# HF_FrontEndOverview.net
KiCad netlist of a schematic drawn in Altium Designer
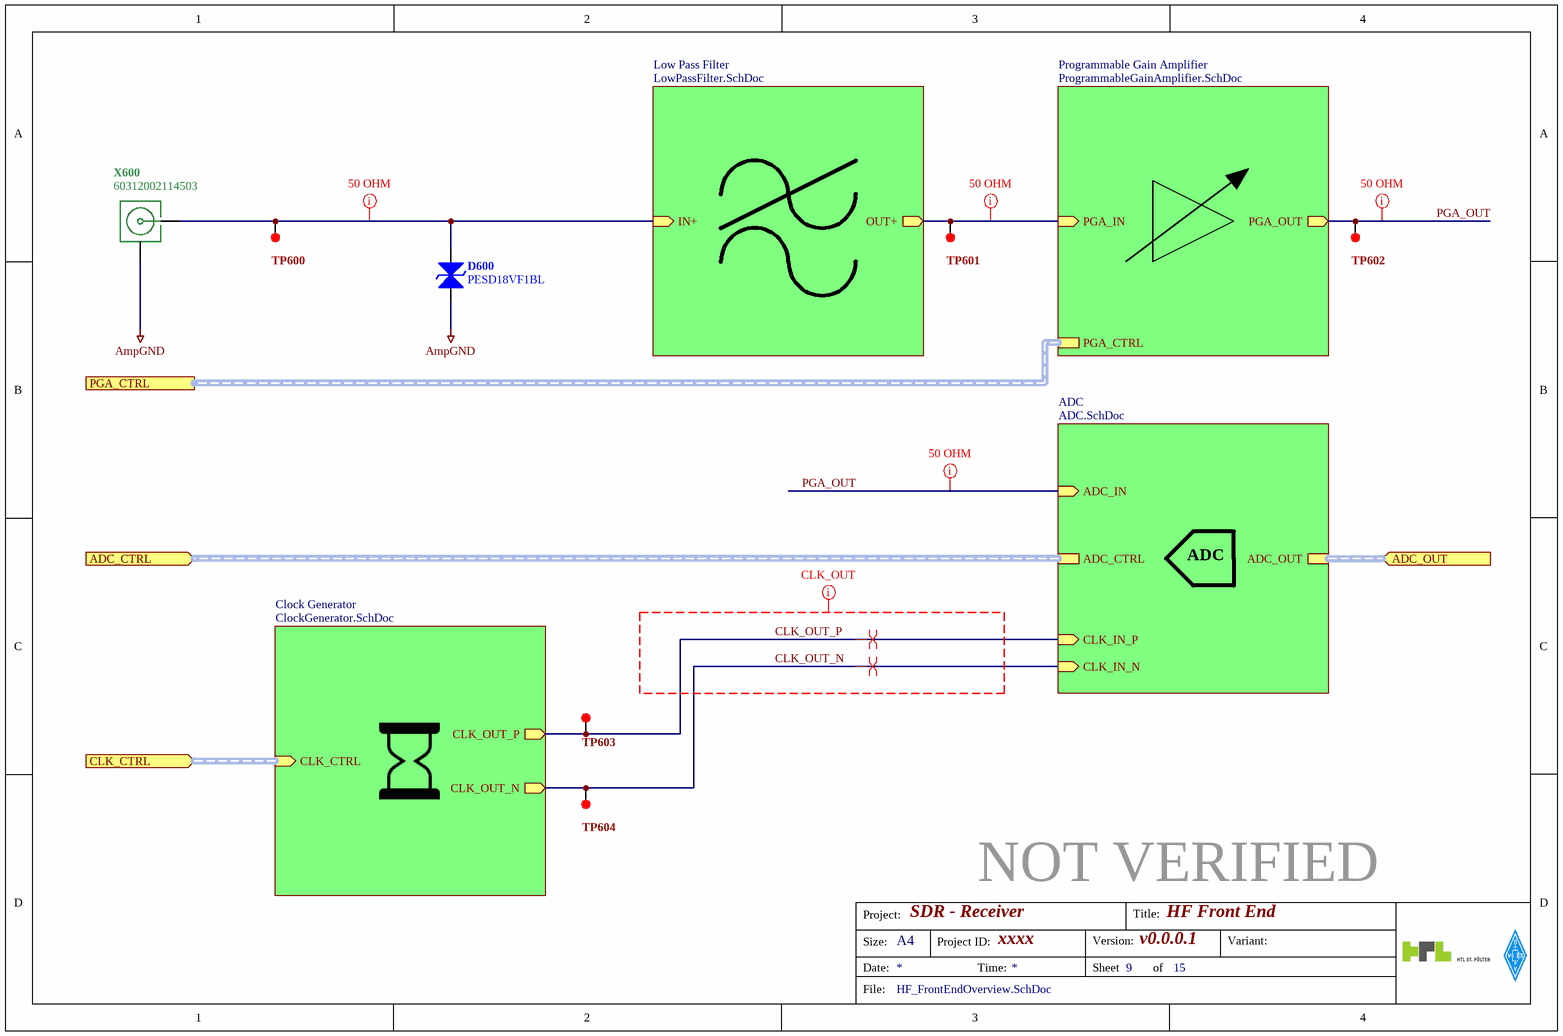
[diagram p0: HF_FrontEndOverview.SchDoc]

(export (version "E")
  (design (tool "Eeschema 10.0.6"))
  (components
    (comp (ref "D600")
      (value "PESD18VF1BL")
      (footprint "DFN65P98X50-2N IPC")
      (libsource (lib "PrometheusLib") (part "D_TVS_PESD18VF1BL"))
    )
    (comp (ref "TP600")
      (value "TP_GENERIC")
      (footprint "PrometheusLib:TP_0.8_P100T")
      (description "Needle Test Point")
      (libsource (lib "PrometheusLib") (part "TP_GENERIC"))
    )
    (comp (ref "TP601")
      (value "TP_GENERIC")
      (footprint "PrometheusLib:TP_0.8_P100T")
      (description "Needle Test Point")
      (libsource (lib "PrometheusLib") (part "TP_GENERIC"))
    )
    (comp (ref "TP602")
      (value "TP_GENERIC")
      (footprint "PrometheusLib:TP_0.8_P100T")
      (description "Needle Test Point")
      (libsource (lib "PrometheusLib") (part "TP_GENERIC"))
    )
    (comp (ref "TP603")
      (value "TP_GENERIC")
      (footprint "PrometheusLib:TP_0.8_P100T")
      (description "Needle Test Point")
      (libsource (lib "PrometheusLib") (part "TP_GENERIC"))
    )
    (comp (ref "TP604")
      (value "TP_GENERIC")
      (footprint "PrometheusLib:TP_0.8_P100T")
      (description "Needle Test Point")
      (libsource (lib "PrometheusLib") (part "TP_GENERIC"))
    )
    (comp (ref "X600")
      (value "60312002114503")
      (footprint "X_60312002114503")
      (description "SMA Jack Straight\r\nType: 348")
      (libsource (lib "PrometheusLib") (part "X_60312002114503"))
    )
  )
  (nets
    (net (code "8") (name "/CLK_OUT_N") (class "Default")
      (node (ref "TP604") (pin "1") (pinfunction "1_1") (pintype "passive"))
    )
    (net (code "9") (name "/CLK_OUT_P") (class "Default")
      (node (ref "TP603") (pin "1") (pinfunction "1_1") (pintype "passive"))
    )
    (net (code "10") (name "/IN+") (class "Default")
      (node (ref "D600") (pin "1") (pinfunction "1_1") (pintype "passive"))
      (node (ref "TP600") (pin "1") (pinfunction "1_1") (pintype "passive"))
      (node (ref "X600") (pin "1") (pinfunction "Sig_1") (pintype "passive"))
    )
    (net (code "11") (name "/OUT+") (class "Default")
      (node (ref "TP601") (pin "1") (pinfunction "1_1") (pintype "passive"))
    )
    (net (code "13") (name "/PGA_OUT") (class "Default")
      (node (ref "TP602") (pin "1") (pinfunction "1_1") (pintype "passive"))
    )
    (net (code "14") (name "AmpGND") (class "Default")
      (node (ref "D600") (pin "2") (pinfunction "2_2") (pintype "passive"))
      (node (ref "X600") (pin "2") (pinfunction "GND_2") (pintype "passive"))
    )
  )
)
